# 03_-_MAIN_BOARD.net
KiCad netlist of a schematic drawn in Altium Designer
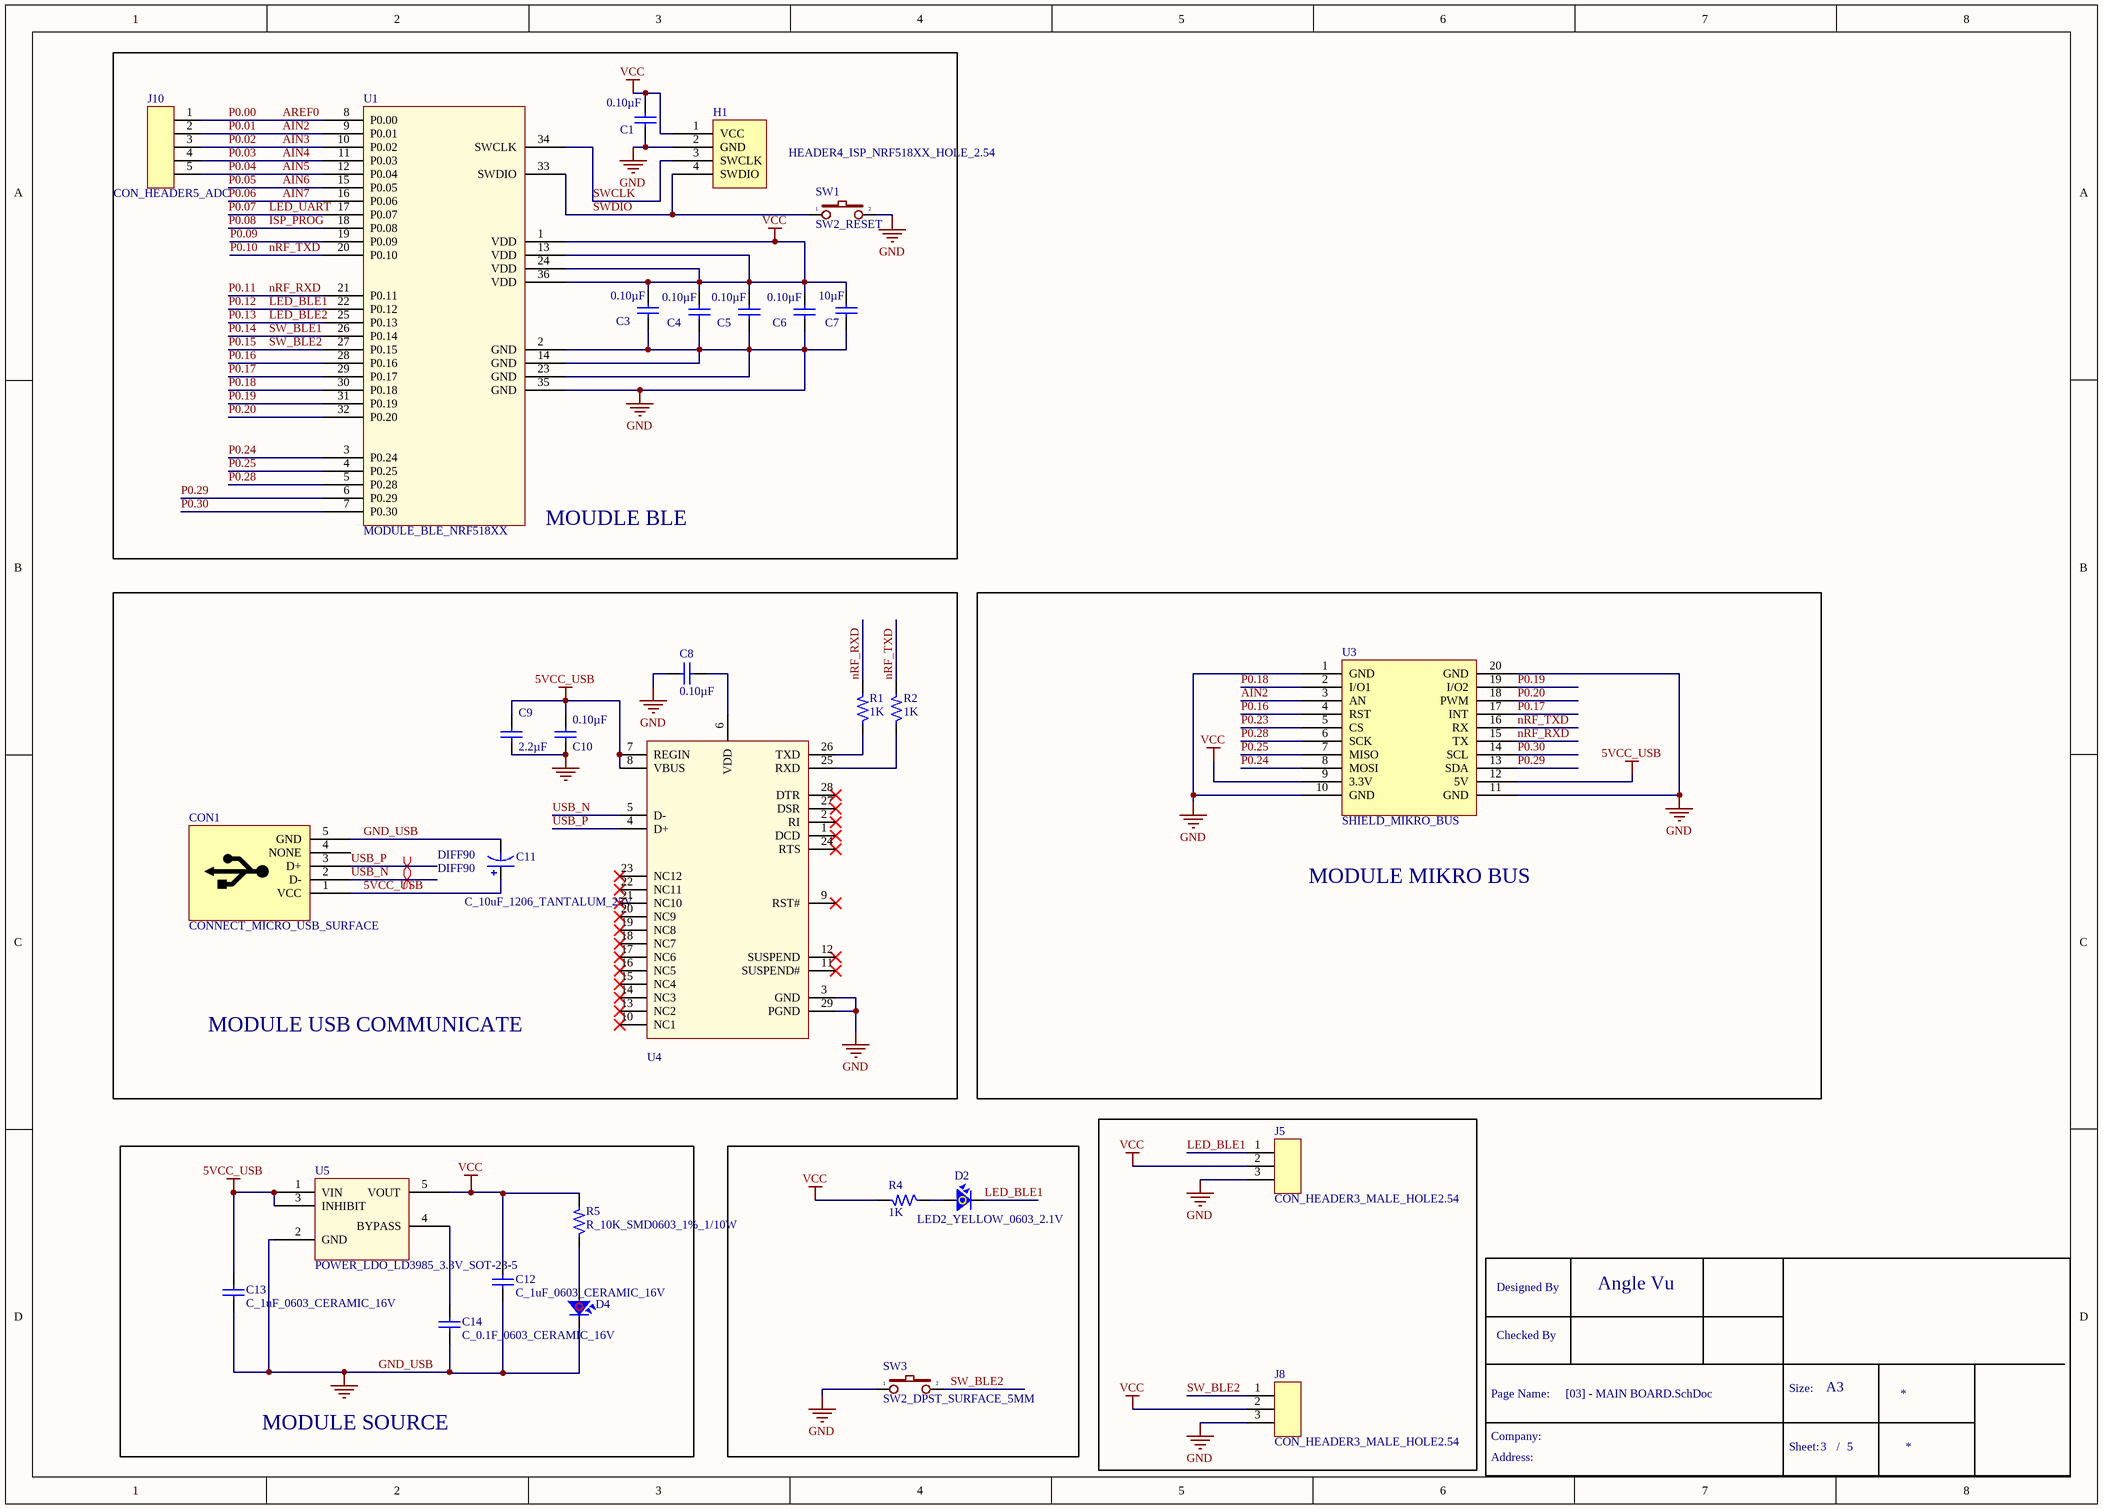
[diagram p0: [03] - MAIN BOARD.SchDoc]

(export (version "E")
  (design (tool "Eeschema 10.0.6"))
  (components
    (comp (ref "C1")
      (value "C_0.1F_0603_CERAMIC_16V")
      (footprint "CAP_SMD0603")
      (description "CAP CER 0.1UF 16V X7R 0603")
      (fields
        (field (name "MANUFACTURER") "Murata Electronics North America")
        (field (name "MANUFACTURER PART NUMBER") "GRM188R71C104KA01D")
        (field (name "CAPACITANCE") "0.10µF")
      )
      (libsource (lib "LIB_ALTIUM") (part "C_0.1F_0603_CERAMIC_16V"))
    )
    (comp (ref "C3")
      (value "C_0.1F_0603_CERAMIC_16V")
      (footprint "CAP_SMD0603")
      (description "CAP CER 0.1UF 16V X7R 0603")
      (fields
        (field (name "MANUFACTURER") "Murata Electronics North America")
        (field (name "MANUFACTURER PART NUMBER") "GRM188R71C104KA01D")
        (field (name "CAPACITANCE") "0.10µF")
      )
      (libsource (lib "LIB_ALTIUM") (part "C_0.1F_0603_CERAMIC_16V"))
    )
    (comp (ref "C4")
      (value "C_0.1F_0603_CERAMIC_16V")
      (footprint "CAP_SMD0603")
      (description "CAP CER 0.1UF 16V X7R 0603")
      (fields
        (field (name "MANUFACTURER") "Murata Electronics North America")
        (field (name "MANUFACTURER PART NUMBER") "GRM188R71C104KA01D")
        (field (name "CAPACITANCE") "0.10µF")
      )
      (libsource (lib "LIB_ALTIUM") (part "C_0.1F_0603_CERAMIC_16V"))
    )
    (comp (ref "C5")
      (value "C_0.1F_0603_CERAMIC_16V")
      (footprint "CAP_SMD0603")
      (description "CAP CER 0.1UF 16V X7R 0603")
      (fields
        (field (name "MANUFACTURER") "Murata Electronics North America")
        (field (name "MANUFACTURER PART NUMBER") "GRM188R71C104KA01D")
        (field (name "CAPACITANCE") "0.10µF")
      )
      (libsource (lib "LIB_ALTIUM") (part "C_0.1F_0603_CERAMIC_16V"))
    )
    (comp (ref "C6")
      (value "C_0.1F_0603_CERAMIC_16V")
      (footprint "CAP_SMD0603")
      (description "CAP CER 0.1UF 16V X7R 0603")
      (fields
        (field (name "MANUFACTURER") "Murata Electronics North America")
        (field (name "MANUFACTURER PART NUMBER") "GRM188R71C104KA01D")
        (field (name "CAPACITANCE") "0.10µF")
      )
      (libsource (lib "LIB_ALTIUM") (part "C_0.1F_0603_CERAMIC_16V"))
    )
    (comp (ref "C7")
      (value "C_10uF_0603_CERAMIC_16V")
      (footprint "CAP_SMD0603")
      (description "CAP CER 10UF 16V X5R 0603")
      (fields
        (field (name "MANUFACTURER") "Murata Electronics North America")
        (field (name "MANUFACTURER PART NUMBER") "GRM188R61C106KAALD")
        (field (name "CAPACITANCE") "10µF")
      )
      (libsource (lib "LIB_ALTIUM") (part "C_10uF_0603_CERAMIC_16V"))
    )
    (comp (ref "C8")
      (value "C_0.1F_0603_CERAMIC_16V")
      (footprint "CAP_SMD0603")
      (description "CAP CER 0.1UF 16V X7R 0603")
      (fields
        (field (name "MANUFACTURER") "Murata Electronics North America")
        (field (name "MANUFACTURER PART NUMBER") "GRM188R71C104KA01D")
        (field (name "CAPACITANCE") "0.10µF")
      )
      (libsource (lib "LIB_ALTIUM") (part "C_0.1F_0603_CERAMIC_16V"))
    )
    (comp (ref "C9")
      (value "C_2.2uF_0603_CERAMIC_16V")
      (footprint "CAP_SMD0603")
      (description "CAP CER 2.2UF 16V X5R 0603")
      (fields
        (field (name "MANUFACTURER") "Murata Electronics North America")
        (field (name "MANUFACTURER PART NUMBER") "GRM188R61C225KE15D")
        (field (name "CAPACITANCE") "2.2µF")
      )
      (libsource (lib "LIB_ALTIUM") (part "C_2.2uF_0603_CERAMIC_16V"))
    )
    (comp (ref "C10")
      (value "C_0.1F_0603_CERAMIC_16V")
      (footprint "CAP_SMD0603")
      (description "CAP CER 0.1UF 16V X7R 0603")
      (fields
        (field (name "MANUFACTURER") "Murata Electronics North America")
        (field (name "MANUFACTURER PART NUMBER") "GRM188R71C104KA01D")
        (field (name "CAPACITANCE") "0.10µF")
      )
      (libsource (lib "LIB_ALTIUM") (part "C_0.1F_0603_CERAMIC_16V"))
    )
    (comp (ref "C11")
      (value "C_10uF_1206_TANTALUM_25V")
      (footprint "CAP_SMD1206_TANTALUM")
      (description "CAP TANT 10UF 25V 10% 1206")
      (fields
        (field (name "MANUFACTURER") "AVX Corporation")
        (field (name "MANUFACTURER PART NUMBER") "F951E106KAAAQ2")
      )
      (libsource (lib "LIB_ALTIUM") (part "C_10uF_1206_TANTALUM_25V"))
    )
    (comp (ref "C12")
      (value "C_1uF_0603_CERAMIC_16V")
      (footprint "CAP_SMD0603")
      (description "CAP CER 1UF 16V X5R 0603")
      (fields
        (field (name "MANUFACTURER") "Murata Electronics North America")
        (field (name "MANUFACTURER PART NUMBER") "GRM188R61C105KA93D")
      )
      (libsource (lib "LIB_ALTIUM") (part "C_1uF_0603_CERAMIC_16V"))
    )
    (comp (ref "C13")
      (value "C_1uF_0603_CERAMIC_16V")
      (footprint "CAP_SMD0603")
      (description "CAP CER 1UF 16V X5R 0603")
      (fields
        (field (name "MANUFACTURER") "Murata Electronics North America")
        (field (name "MANUFACTURER PART NUMBER") "GRM188R61C105KA93D")
      )
      (libsource (lib "LIB_ALTIUM") (part "C_1uF_0603_CERAMIC_16V"))
    )
    (comp (ref "C14")
      (value "C_0.1F_0603_CERAMIC_16V")
      (footprint "CAP_SMD0603")
      (description "CAP CER 0.1UF 16V X7R 0603")
      (fields
        (field (name "MANUFACTURER") "Murata Electronics North America")
        (field (name "MANUFACTURER PART NUMBER") "GRM188R71C104KA01D")
      )
      (libsource (lib "LIB_ALTIUM") (part "C_0.1F_0603_CERAMIC_16V"))
    )
    (comp (ref "CON1")
      (value "CONNECT_MICRO_USB_SURFACE")
      (footprint "CON_MICRO_USB_HOLE")
      (description "CONN RCPT STD MICRO USB TYPE B")
      (fields
        (field (name "MANUFACTURER") "Amphenol FCI")
        (field (name "MANUFACTURER PART NUMBER") "10103593-0001LF")
      )
      (libsource (lib "LIB_ALTIUM") (part "CONNECT_MICRO_USB_SURFACE"))
    )
    (comp (ref "D2")
      (value "LED2_YELLOW_0603_2.1V")
      (footprint "LED_YELLOW_SMD0603")
      (description "LED YELLOW CLEAR 0603 SMD")
      (fields
        (field (name "MANUFACTURER") "Lite-On Inc.")
        (field (name "MANUFACTURER PART NUMBER") "LTST-C191KSKT")
      )
      (libsource (lib "LIB_ALTIUM") (part "LED2_YELLOW_0603_2.1V"))
    )
    (comp (ref "D4")
      (value "LED2_RED_0603_2V")
      (footprint "LED_RED_SMD0603")
      (description "LED RED CLEAR 0603 SMD")
      (fields
        (field (name "MANUFACTURER") "Lite-On Inc.")
        (field (name "MANUFACTURER PART NUMBER") "LTST-C191KRKT")
      )
      (libsource (lib "LIB_ALTIUM") (part "LED2_RED_0603_2V"))
    )
    (comp (ref "H1")
      (value "HEADER4_ISP_NRF518XX_HOLE_2.54")
      (footprint "HEADER4_ISP_HOLE_2.54")
      (description "CONN HEADER 4POS .100 STR TIN")
      (fields
        (field (name "MANUFACTURER") "Amphenol FCI")
        (field (name "MANUFACTURER PART NUMBER") "68002-404HLF")
      )
      (libsource (lib "LIB_ALTIUM") (part "HEADER4_ISP_NRF518XX_HOLE_2.54"))
    )
    (comp (ref "J5")
      (value "CON_HEADER3_MALE_HOLE2.54")
      (footprint "CON_HEADER3_HOLE_2.54")
      (description "CON_HEADER10_HOLE2.54")
      (fields (field (name "MANUFACTURER") "3M") (field (name "MANUFACTURER PART NUMBER") "961102-6404-AR"))
      (libsource (lib "LIB_ALTIUM") (part "CON_HEADER3_MALE_HOLE2.54"))
    )
    (comp (ref "J8")
      (value "CON_HEADER3_MALE_HOLE2.54")
      (footprint "CON_HEADER3_HOLE_2.54")
      (description "CON_HEADER10_HOLE2.54")
      (fields (field (name "MANUFACTURER") "3M") (field (name "MANUFACTURER PART NUMBER") "961102-6404-AR"))
      (libsource (lib "LIB_ALTIUM") (part "CON_HEADER3_MALE_HOLE2.54"))
    )
    (comp (ref "J10")
      (value "CON_HEADER5_ADC")
      (footprint "CON_HEADER5_HOLE_2.54")
      (description "CON_HEADER10_HOLE2.54")
      (fields (field (name "MANUFACTURER") "3M") (field (name "MANUFACTURER PART NUMBER") "961102-6404-AR"))
      (libsource (lib "LIB_ALTIUM") (part "CON_HEADER5_MALE_HOLE2.54"))
    )
    (comp (ref "R1")
      (value "R_1K2_SMD0603_1%_1/10W")
      (footprint "RES_SMD0603")
      (description "RES SMD 1.2K OHM 1% 1/10W 0603")
      (fields
        (field (name "MANUFACTURER") "Yageo")
        (field (name "MANUFACTURER PART NUMBER") "RC0603FR-071K2L")
        (field (name "RESISTANCE (OHMS)") "1K")
      )
      (libsource (lib "LIB_ALTIUM") (part "R_1K2_SMD0603_1%_1/10W"))
    )
    (comp (ref "R2")
      (value "R_1K2_SMD0603_1%_1/10W")
      (footprint "RES_SMD0603")
      (description "RES SMD 1.2K OHM 1% 1/10W 0603")
      (fields
        (field (name "MANUFACTURER") "Yageo")
        (field (name "MANUFACTURER PART NUMBER") "RC0603FR-071K2L")
        (field (name "RESISTANCE (OHMS)") "1K")
      )
      (libsource (lib "LIB_ALTIUM") (part "R_1K2_SMD0603_1%_1/10W"))
    )
    (comp (ref "R4")
      (value "R_1K2_SMD0603_1%_1/10W")
      (footprint "RES_SMD0603")
      (description "RES SMD 1.2K OHM 1% 1/10W 0603")
      (fields
        (field (name "MANUFACTURER") "Yageo")
        (field (name "MANUFACTURER PART NUMBER") "RC0603FR-071K2L")
        (field (name "RESISTANCE (OHMS)") "1K")
      )
      (libsource (lib "LIB_ALTIUM") (part "R_1K2_SMD0603_1%_1/10W"))
    )
    (comp (ref "R5")
      (value "R_10K_SMD0603_1%_1/10W")
      (footprint "RES_SMD0603")
      (description "RES SMD 10K OHM 1% 1/10W 0603")
      (fields
        (field (name "MANUFACTURER") "Yageo")
        (field (name "MANUFACTURER PART NUMBER") "RC0603FR-0710KL")
      )
      (libsource (lib "LIB_ALTIUM") (part "R_10K_SMD0603_1%_1/10W"))
    )
    (comp (ref "SW1")
      (value "SW2_RESET")
      (footprint "SW2-SMD")
      (description "SWITCH TACTILE SPST-NO 0.05A 12V")
      (fields
        (field (name "MANUFACTURER") "Wurth Electronics Inc")
        (field (name "MANUFACTURER PART NUMBER") "434121050836")
      )
      (libsource (lib "LIB_ALTIUM") (part "SW2_DPST_SURFACE_5MM"))
    )
    (comp (ref "SW3")
      (value "SW2_DPST_SURFACE_5MM")
      (footprint "SW2-SMD")
      (description "SWITCH TACTILE SPST-NO 0.05A 12V")
      (fields
        (field (name "MANUFACTURER") "Wurth Electronics Inc")
        (field (name "MANUFACTURER PART NUMBER") "434121050836")
      )
      (libsource (lib "LIB_ALTIUM") (part "SW2_DPST_SURFACE_5MM"))
    )
    (comp (ref "U1")
      (value "MODULE_BLE_NRF518XX")
      (footprint "MODULE_NRF518xx")
      (libsource (lib "LIB_ALTIUM") (part "MODULE_BLE_NRF518XX"))
    )
    (comp (ref "U3")
      (value "SHIELD_MIKRO_BUS")
      (footprint "SHIELD_MIKRO_BUS")
      (libsource (lib "SchematicLib") (part "SHIELD_MIKRO_BUS"))
    )
    (comp (ref "U4")
      (value "USB_CP2102-GMR")
      (footprint "QFN_28PIN_USBC2102")
      (description "IC USB-TO-UART BRIDGE 28VQFN")
      (fields
        (field (name "MANUFACTURER") "Silicon Labs")
        (field (name "MANUFACTURER PART NUMBER") "CP2102-GMR")
      )
      (libsource (lib "LIB_ALTIUM") (part "USB_CP2102-GMR"))
    )
    (comp (ref "U5")
      (value "POWER_LDO_LD3985_3.3V_SOT-23-5")
      (footprint "POWER_LDO_LDR3985-3.3")
      (description "IC REG LDO 3.3V 0.15A SOT23-5")
      (fields
        (field (name "MANUFACTURER") "STMicroelectronics")
        (field (name "MANUFACTURER PART NUMBER") "LD3985M33R")
      )
      (libsource (lib "LIB_ALTIUM") (part "POWER_LDO_LD3985_3.3V_SOT-23-5"))
    )
  )
  (nets
    (net (code "1") (name "/AIN2") (class "Default")
      (node (ref "J10") (pin "2") (pinfunction "SIGN-_2") (pintype "passive"))
      (node (ref "U1") (pin "9") (pinfunction "P0.01_9") (pintype "passive"))
      (node (ref "U3") (pin "3") (pinfunction "AN_3") (pintype "passive"))
    )
    (net (code "2") (name "/AIN3") (class "Default")
      (node (ref "J10") (pin "3") (pinfunction "3_3") (pintype "passive"))
      (node (ref "U1") (pin "10") (pinfunction "P0.02_10") (pintype "passive"))
    )
    (net (code "3") (name "/AIN4") (class "Default")
      (node (ref "J10") (pin "4") (pinfunction "4_4") (pintype "passive"))
      (node (ref "U1") (pin "11") (pinfunction "P0.03_11") (pintype "passive"))
    )
    (net (code "4") (name "/AIN5") (class "Default")
      (node (ref "J10") (pin "5") (pinfunction "5_5") (pintype "passive"))
      (node (ref "U1") (pin "12") (pinfunction "P0.04_12") (pintype "passive"))
    )
    (net (code "5") (name "/AIN6") (class "Default")
      (node (ref "U1") (pin "15") (pinfunction "P0.05_15") (pintype "passive"))
    )
    (net (code "6") (name "/AIN7") (class "Default")
      (node (ref "U1") (pin "16") (pinfunction "P0.06_16") (pintype "passive"))
    )
    (net (code "7") (name "/AREF0") (class "Default")
      (node (ref "J10") (pin "1") (pinfunction "SIGN+_1") (pintype "passive"))
      (node (ref "U1") (pin "8") (pinfunction "P0.00_8") (pintype "passive"))
    )
    (net (code "8") (name "/ISP_PROG") (class "Default")
      (node (ref "U1") (pin "18") (pinfunction "P0.08_18") (pintype "passive"))
    )
    (net (code "9") (name "/LED_BLE1") (class "Default")
      (node (ref "D2") (pin "2") (pinfunction "2_2") (pintype "passive"))
      (node (ref "J5") (pin "1") (pinfunction "SIGN+_1") (pintype "passive"))
      (node (ref "U1") (pin "22") (pinfunction "P0.12_22") (pintype "passive"))
    )
    (net (code "10") (name "/LED_BLE2") (class "Default")
      (node (ref "U1") (pin "25") (pinfunction "P0.13_25") (pintype "passive"))
    )
    (net (code "11") (name "/LED_UART") (class "Default")
      (node (ref "U1") (pin "17") (pinfunction "P0.07_17") (pintype "passive"))
    )
    (net (code "12") (name "/P0.09") (class "Default")
      (node (ref "U1") (pin "19") (pinfunction "P0.09_19") (pintype "passive"))
    )
    (net (code "13") (name "/P0.10") (class "Default")
      (node (ref "R2") (pin "2") (pinfunction "2_2") (pintype "passive"))
      (node (ref "U1") (pin "20") (pinfunction "P0.10_20") (pintype "passive"))
      (node (ref "U3") (pin "16") (pinfunction "RX_16") (pintype "passive"))
    )
    (net (code "14") (name "/P0.11") (class "Default")
      (node (ref "R1") (pin "2") (pinfunction "2_2") (pintype "passive"))
      (node (ref "U1") (pin "21") (pinfunction "P0.11_21") (pintype "passive"))
      (node (ref "U3") (pin "15") (pinfunction "TX_15") (pintype "passive"))
    )
    (net (code "15") (name "/P0.14") (class "Default")
      (node (ref "U1") (pin "26") (pinfunction "P0.14_26") (pintype "passive"))
    )
    (net (code "16") (name "/P0.15") (class "Default")
      (node (ref "J8") (pin "1") (pinfunction "SIGN+_1") (pintype "passive"))
      (node (ref "SW3") (pin "2") (pinfunction "2_2") (pintype "passive"))
      (node (ref "U1") (pin "27") (pinfunction "P0.15_27") (pintype "passive"))
    )
    (net (code "17") (name "/P0.16") (class "Default")
      (node (ref "U1") (pin "28") (pinfunction "P0.16_28") (pintype "passive"))
      (node (ref "U3") (pin "4") (pinfunction "RST_4") (pintype "passive"))
    )
    (net (code "18") (name "/P0.17") (class "Default")
      (node (ref "U1") (pin "29") (pinfunction "P0.17_29") (pintype "passive"))
      (node (ref "U3") (pin "17") (pinfunction "INT_17") (pintype "passive"))
    )
    (net (code "19") (name "/P0.18") (class "Default")
      (node (ref "U1") (pin "30") (pinfunction "P0.18_30") (pintype "passive"))
      (node (ref "U3") (pin "2") (pinfunction "I/O1_2") (pintype "passive"))
    )
    (net (code "20") (name "/P0.19") (class "Default")
      (node (ref "U1") (pin "31") (pinfunction "P0.19_31") (pintype "passive"))
      (node (ref "U3") (pin "19") (pinfunction "I/O2_19") (pintype "passive"))
    )
    (net (code "21") (name "/P0.20") (class "Default")
      (node (ref "U1") (pin "32") (pinfunction "P0.20_32") (pintype "passive"))
      (node (ref "U3") (pin "18") (pinfunction "PWM_18") (pintype "passive"))
    )
    (net (code "22") (name "/P0.23") (class "Default")
      (node (ref "U3") (pin "5") (pinfunction "CS_5") (pintype "passive"))
    )
    (net (code "23") (name "/P0.24") (class "Default")
      (node (ref "U1") (pin "3") (pinfunction "P0.24_3") (pintype "passive"))
      (node (ref "U3") (pin "8") (pinfunction "MOSI_8") (pintype "passive"))
    )
    (net (code "24") (name "/P0.25") (class "Default")
      (node (ref "U1") (pin "4") (pinfunction "P0.25_4") (pintype "passive"))
      (node (ref "U3") (pin "7") (pinfunction "MISO_7") (pintype "passive"))
    )
    (net (code "25") (name "/P0.28") (class "Default")
      (node (ref "U1") (pin "5") (pinfunction "P0.28_5") (pintype "passive"))
      (node (ref "U3") (pin "6") (pinfunction "SCK_6") (pintype "passive"))
    )
    (net (code "26") (name "/P0.29") (class "Default")
      (node (ref "U1") (pin "6") (pinfunction "P0.29_6") (pintype "passive"))
      (node (ref "U3") (pin "13") (pinfunction "SDA_13") (pintype "passive"))
    )
    (net (code "27") (name "/P0.30") (class "Default")
      (node (ref "U1") (pin "7") (pinfunction "P0.30_7") (pintype "passive"))
      (node (ref "U3") (pin "14") (pinfunction "SCL_14") (pintype "passive"))
    )
    (net (code "28") (name "/SWCLK") (class "Default")
      (node (ref "H1") (pin "3") (pinfunction "SWCLK_3") (pintype "passive"))
      (node (ref "U1") (pin "34") (pinfunction "SWCLK_34") (pintype "passive"))
    )
    (net (code "29") (name "/SWDIO") (class "Default")
      (node (ref "H1") (pin "4") (pinfunction "SWDIO_4") (pintype "passive"))
      (node (ref "SW1") (pin "1") (pinfunction "1_1") (pintype "passive"))
      (node (ref "U1") (pin "33") (pinfunction "SWDIO_33") (pintype "passive"))
    )
    (net (code "30") (name "/USB_N") (class "Default")
      (node (ref "CON1") (pin "2") (pinfunction "D-_2") (pintype "passive"))
      (node (ref "U4") (pin "5") (pinfunction "D-_5") (pintype "passive"))
    )
    (net (code "31") (name "/USB_P") (class "Default")
      (node (ref "CON1") (pin "3") (pinfunction "D+_3") (pintype "passive"))
      (node (ref "U4") (pin "4") (pinfunction "D+_4") (pintype "passive"))
    )
    (net (code "32") (name "5VCC_USB") (class "Default")
      (node (ref "C10") (pin "2") (pinfunction "2_2") (pintype "passive"))
      (node (ref "C11") (pin "1") (pinfunction "1_1") (pintype "passive"))
      (node (ref "C13") (pin "2") (pinfunction "2_2") (pintype "passive"))
      (node (ref "C9") (pin "2") (pinfunction "2_2") (pintype "passive"))
      (node (ref "CON1") (pin "1") (pinfunction "VCC_1") (pintype "passive"))
      (node (ref "U3") (pin "12") (pinfunction "5V_12") (pintype "passive"))
      (node (ref "U4") (pin "7") (pinfunction "REGIN_7") (pintype "passive"))
      (node (ref "U4") (pin "8") (pinfunction "VBUS_8") (pintype "passive"))
      (node (ref "U5") (pin "1") (pinfunction "VIN_1") (pintype "passive"))
      (node (ref "U5") (pin "3") (pinfunction "INHIBIT_3") (pintype "passive"))
    )
    (net (code "33") (name "GND") (class "Default")
      (node (ref "C1") (pin "1") (pinfunction "1_1") (pintype "passive"))
      (node (ref "C10") (pin "1") (pinfunction "1_1") (pintype "passive"))
      (node (ref "C11") (pin "2") (pinfunction "2_2") (pintype "passive"))
      (node (ref "C12") (pin "1") (pinfunction "1_1") (pintype "passive"))
      (node (ref "C13") (pin "1") (pinfunction "1_1") (pintype "passive"))
      (node (ref "C14") (pin "1") (pinfunction "1_1") (pintype "passive"))
      (node (ref "C3") (pin "1") (pinfunction "1_1") (pintype "passive"))
      (node (ref "C4") (pin "1") (pinfunction "1_1") (pintype "passive"))
      (node (ref "C5") (pin "1") (pinfunction "1_1") (pintype "passive"))
      (node (ref "C6") (pin "1") (pinfunction "1_1") (pintype "passive"))
      (node (ref "C7") (pin "1") (pinfunction "1_1") (pintype "passive"))
      (node (ref "C8") (pin "2") (pinfunction "2_2") (pintype "passive"))
      (node (ref "C9") (pin "1") (pinfunction "1_1") (pintype "passive"))
      (node (ref "CON1") (pin "5") (pinfunction "GND_5") (pintype "passive"))
      (node (ref "D4") (pin "2") (pinfunction "2_2") (pintype "passive"))
      (node (ref "H1") (pin "2") (pinfunction "GND_2") (pintype "passive"))
      (node (ref "J5") (pin "3") (pinfunction "3_3") (pintype "passive"))
      (node (ref "J8") (pin "3") (pinfunction "3_3") (pintype "passive"))
      (node (ref "SW1") (pin "2") (pinfunction "2_2") (pintype "passive"))
      (node (ref "SW3") (pin "1") (pinfunction "1_1") (pintype "passive"))
      (node (ref "U1") (pin "14") (pinfunction "GND_14") (pintype "passive"))
      (node (ref "U1") (pin "2") (pinfunction "GND_2") (pintype "passive"))
      (node (ref "U1") (pin "23") (pinfunction "GND_23") (pintype "passive"))
      (node (ref "U1") (pin "35") (pinfunction "GND_35") (pintype "passive"))
      (node (ref "U3") (pin "1") (pinfunction "GND_1") (pintype "passive"))
      (node (ref "U3") (pin "10") (pinfunction "GND_10") (pintype "passive"))
      (node (ref "U3") (pin "11") (pinfunction "GND_11") (pintype "passive"))
      (node (ref "U3") (pin "20") (pinfunction "GND_20") (pintype "passive"))
      (node (ref "U4") (pin "29") (pinfunction "PGND_29") (pintype "passive"))
      (node (ref "U4") (pin "3") (pinfunction "GND_3") (pintype "passive"))
      (node (ref "U5") (pin "2") (pinfunction "GND_2") (pintype "passive"))
    )
    (net (code "34") (name "Net-(D2-Pad1)") (class "Default")
      (node (ref "D2") (pin "1") (pinfunction "1_1") (pintype "passive"))
      (node (ref "R4") (pin "1") (pinfunction "1_1") (pintype "passive"))
    )
    (net (code "35") (name "Net-(D4-Pad1)") (class "Default")
      (node (ref "D4") (pin "1") (pinfunction "1_1") (pintype "passive"))
      (node (ref "R5") (pin "1") (pinfunction "1_1") (pintype "passive"))
    )
    (net (code "36") (name "Net-(U4-RXD)") (class "Default")
      (node (ref "R2") (pin "1") (pinfunction "1_1") (pintype "passive"))
      (node (ref "U4") (pin "25") (pinfunction "RXD_25") (pintype "passive"))
    )
    (net (code "37") (name "Net-(U4-TXD)") (class "Default")
      (node (ref "R1") (pin "1") (pinfunction "1_1") (pintype "passive"))
      (node (ref "U4") (pin "26") (pinfunction "TXD_26") (pintype "passive"))
    )
    (net (code "38") (name "Net-(U4-VDD)") (class "Default")
      (node (ref "C8") (pin "1") (pinfunction "1_1") (pintype "passive"))
      (node (ref "U4") (pin "6") (pinfunction "VDD_6") (pintype "passive"))
    )
    (net (code "39") (name "Net-(U5-BYPASS)") (class "Default")
      (node (ref "C14") (pin "2") (pinfunction "2_2") (pintype "passive"))
      (node (ref "U5") (pin "4") (pinfunction "BYPASS_4") (pintype "passive"))
    )
    (net (code "40") (name "VCC") (class "Default")
      (node (ref "C1") (pin "2") (pinfunction "2_2") (pintype "passive"))
      (node (ref "C12") (pin "2") (pinfunction "2_2") (pintype "passive"))
      (node (ref "C3") (pin "2") (pinfunction "2_2") (pintype "passive"))
      (node (ref "C4") (pin "2") (pinfunction "2_2") (pintype "passive"))
      (node (ref "C5") (pin "2") (pinfunction "2_2") (pintype "passive"))
      (node (ref "C6") (pin "2") (pinfunction "2_2") (pintype "passive"))
      (node (ref "C7") (pin "2") (pinfunction "2_2") (pintype "passive"))
      (node (ref "H1") (pin "1") (pinfunction "VCC_1") (pintype "passive"))
      (node (ref "J5") (pin "2") (pinfunction "SIGN-_2") (pintype "passive"))
      (node (ref "J8") (pin "2") (pinfunction "SIGN-_2") (pintype "passive"))
      (node (ref "R4") (pin "2") (pinfunction "2_2") (pintype "passive"))
      (node (ref "R5") (pin "2") (pinfunction "2_2") (pintype "passive"))
      (node (ref "U1") (pin "1") (pinfunction "VDD_1") (pintype "passive"))
      (node (ref "U1") (pin "13") (pinfunction "VDD_13") (pintype "passive"))
      (node (ref "U1") (pin "24") (pinfunction "VDD_24") (pintype "passive"))
      (node (ref "U1") (pin "36") (pinfunction "VDD_36") (pintype "passive"))
      (node (ref "U3") (pin "9") (pinfunction "3.3V_9") (pintype "passive"))
      (node (ref "U5") (pin "5") (pinfunction "VOUT_5") (pintype "passive"))
    )
    (net (code "41") (name "unconnected-(CON1-NONE-Pad4)") (class "Default")
      (node (ref "CON1") (pin "4") (pinfunction "NONE_4") (pintype "passive"))
    )
    (net (code "42") (name "unconnected-(U4-DCD-Pad1)") (class "Default")
      (node (ref "U4") (pin "1") (pinfunction "DCD_1") (pintype "passive+no_connect"))
    )
    (net (code "43") (name "unconnected-(U4-DSR-Pad27)") (class "Default")
      (node (ref "U4") (pin "27") (pinfunction "DSR_27") (pintype "passive+no_connect"))
    )
    (net (code "44") (name "unconnected-(U4-DTR-Pad28)") (class "Default")
      (node (ref "U4") (pin "28") (pinfunction "DTR_28") (pintype "passive+no_connect"))
    )
    (net (code "45") (name "unconnected-(U4-NC1-Pad10)") (class "Default")
      (node (ref "U4") (pin "10") (pinfunction "NC1_10") (pintype "passive+no_connect"))
    )
    (net (code "46") (name "unconnected-(U4-NC2-Pad13)") (class "Default")
      (node (ref "U4") (pin "13") (pinfunction "NC2_13") (pintype "passive+no_connect"))
    )
    (net (code "47") (name "unconnected-(U4-NC3-Pad14)") (class "Default")
      (node (ref "U4") (pin "14") (pinfunction "NC3_14") (pintype "passive+no_connect"))
    )
    (net (code "48") (name "unconnected-(U4-NC4-Pad15)") (class "Default")
      (node (ref "U4") (pin "15") (pinfunction "NC4_15") (pintype "passive+no_connect"))
    )
    (net (code "49") (name "unconnected-(U4-NC5-Pad16)") (class "Default")
      (node (ref "U4") (pin "16") (pinfunction "NC5_16") (pintype "passive+no_connect"))
    )
    (net (code "50") (name "unconnected-(U4-NC6-Pad17)") (class "Default")
      (node (ref "U4") (pin "17") (pinfunction "NC6_17") (pintype "passive+no_connect"))
    )
    (net (code "51") (name "unconnected-(U4-NC7-Pad18)") (class "Default")
      (node (ref "U4") (pin "18") (pinfunction "NC7_18") (pintype "passive+no_connect"))
    )
    (net (code "52") (name "unconnected-(U4-NC8-Pad19)") (class "Default")
      (node (ref "U4") (pin "19") (pinfunction "NC8_19") (pintype "passive+no_connect"))
    )
    (net (code "53") (name "unconnected-(U4-NC9-Pad20)") (class "Default")
      (node (ref "U4") (pin "20") (pinfunction "NC9_20") (pintype "passive+no_connect"))
    )
    (net (code "54") (name "unconnected-(U4-NC10-Pad21)") (class "Default")
      (node (ref "U4") (pin "21") (pinfunction "NC10_21") (pintype "passive+no_connect"))
    )
    (net (code "55") (name "unconnected-(U4-NC11-Pad22)") (class "Default")
      (node (ref "U4") (pin "22") (pinfunction "NC11_22") (pintype "passive+no_connect"))
    )
    (net (code "56") (name "unconnected-(U4-NC12-Pad23)") (class "Default")
      (node (ref "U4") (pin "23") (pinfunction "NC12_23") (pintype "passive+no_connect"))
    )
    (net (code "57") (name "unconnected-(U4-RI-Pad2)") (class "Default")
      (node (ref "U4") (pin "2") (pinfunction "RI_2") (pintype "passive+no_connect"))
    )
    (net (code "58") (name "unconnected-(U4-RST#-Pad9)") (class "Default")
      (node (ref "U4") (pin "9") (pinfunction "RST#_9") (pintype "passive+no_connect"))
    )
    (net (code "59") (name "unconnected-(U4-RTS-Pad24)") (class "Default")
      (node (ref "U4") (pin "24") (pinfunction "RTS_24") (pintype "passive+no_connect"))
    )
    (net (code "60") (name "unconnected-(U4-SUSPEND#-Pad11)") (class "Default")
      (node (ref "U4") (pin "11") (pinfunction "SUSPEND#_11") (pintype "passive+no_connect"))
    )
    (net (code "61") (name "unconnected-(U4-SUSPEND-Pad12)") (class "Default")
      (node (ref "U4") (pin "12") (pinfunction "SUSPEND_12") (pintype "passive+no_connect"))
    )
  )
)
